# STM32F103CBT6.net
KiCad netlist of a schematic drawn in Altium Designer
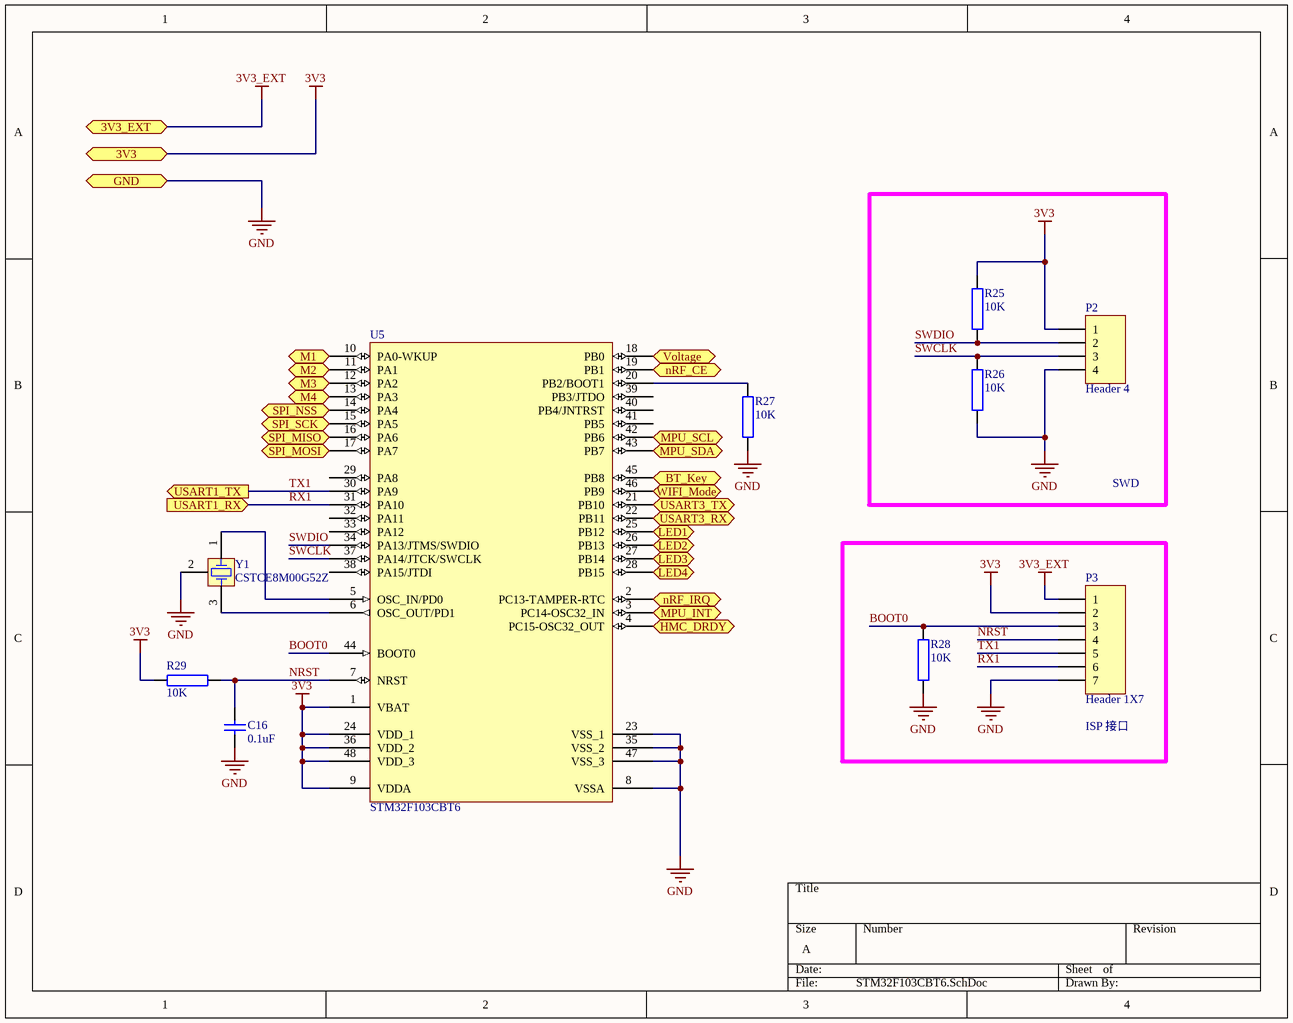
[diagram p0: STM32F103CBT6.SchDoc]

(export (version "E")
  (design (tool "Eeschema 10.0.6"))
  (components
    (comp (ref "C16")
      (value "0.1uF")
      (footprint "C0603")
      (description "Capacitor (Semiconductor SIM Model)")
      (fields (field (name "PUBLISHER") "Altium Limited"))
      (libsource (lib "Quadcopter") (part "Cap"))
    )
    (comp (ref "P2")
      (value "Header 4")
      (footprint "HDR1X4")
      (description "Header, 4-Pin")
      (fields (field (name "PUBLISHER") "Altium Limited"))
      (libsource (lib "Miscellaneous Connectors") (part "Header 4"))
    )
    (comp (ref "P3")
      (value "Header 1X7")
      (footprint "HDR1X7")
      (description "Header, 7-Pin")
      (fields (field (name "PUBLISHER") "Altium Limited"))
      (libsource (lib "Quadcopter") (part "Header 1X7"))
    )
    (comp (ref "R25")
      (value "10K")
      (footprint "R0603")
      (description "Resistor")
      (fields (field (name "PUBLISHER") "Altium Limited"))
      (libsource (lib "Quadcopter") (part "Res3"))
    )
    (comp (ref "R26")
      (value "10K")
      (footprint "R0603")
      (description "Resistor")
      (fields (field (name "PUBLISHER") "Altium Limited"))
      (libsource (lib "Quadcopter") (part "Res3"))
    )
    (comp (ref "R27")
      (value "10K")
      (footprint "R0603")
      (description "Resistor")
      (fields (field (name "PUBLISHER") "Altium Limited"))
      (libsource (lib "Quadcopter") (part "Res3"))
    )
    (comp (ref "R28")
      (value "10K")
      (footprint "R0603")
      (description "Resistor")
      (fields (field (name "PUBLISHER") "Altium Limited"))
      (libsource (lib "Quadcopter") (part "Res3"))
    )
    (comp (ref "R29")
      (value "10K")
      (footprint "R0603")
      (description "Resistor")
      (fields (field (name "PUBLISHER") "Altium Limited"))
      (libsource (lib "Quadcopter") (part "Res3"))
    )
    (comp (ref "U5")
      (value "STM32F103CBT6")
      (footprint "LQFP48_N")
      (description "STM32 ARM-based 32-bit MCU with 128 Kbytes Flash, 48-pin LQFP, Industrial Temperature")
      (fields (field (name "PUBLISHER") "Altium Limited"))
      (libsource (lib "ST Microcontroller 32-Bit STM32") (part "STM32F103CBT6"))
    )
    (comp (ref "Y1")
      (value "CSTCE8M00G52Z")
      (footprint "X8MCSTCR")
      (description "Crystal Oscillator, 3rd In-Line Lead Version")
      (libsource (lib "Quadcopter") (part "CSTCE8M00G52Z"))
    )
  )
  (nets
    (net (code "1") (name "/BOOT0") (class "Default")
      (node (ref "P3") (pin "3") (pinfunction "3_3") (pintype "passive"))
      (node (ref "R28") (pin "1") (pinfunction "1_1") (pintype "passive"))
      (node (ref "U5") (pin "44") (pinfunction "BOOT0_44") (pintype "input"))
    )
    (net (code "2") (name "/BT_Key") (class "Default")
      (node (ref "U5") (pin "45") (pinfunction "PB8_45") (pintype "bidirectional"))
    )
    (net (code "3") (name "/HMC_DRDY") (class "Default")
      (node (ref "U5") (pin "4") (pinfunction "PC15-OSC32_OUT_4") (pintype "bidirectional"))
    )
    (net (code "4") (name "/LED1") (class "Default")
      (node (ref "U5") (pin "25") (pinfunction "PB12_25") (pintype "bidirectional"))
    )
    (net (code "5") (name "/LED2") (class "Default")
      (node (ref "U5") (pin "26") (pinfunction "PB13_26") (pintype "bidirectional"))
    )
    (net (code "6") (name "/LED3") (class "Default")
      (node (ref "U5") (pin "27") (pinfunction "PB14_27") (pintype "bidirectional"))
    )
    (net (code "7") (name "/LED4") (class "Default")
      (node (ref "U5") (pin "28") (pinfunction "PB15_28") (pintype "bidirectional"))
    )
    (net (code "8") (name "/M1") (class "Default")
      (node (ref "U5") (pin "10") (pinfunction "PA0-WKUP_10") (pintype "bidirectional"))
    )
    (net (code "9") (name "/M2") (class "Default")
      (node (ref "U5") (pin "11") (pinfunction "PA1_11") (pintype "bidirectional"))
    )
    (net (code "10") (name "/M3") (class "Default")
      (node (ref "U5") (pin "12") (pinfunction "PA2_12") (pintype "bidirectional"))
    )
    (net (code "11") (name "/M4") (class "Default")
      (node (ref "U5") (pin "13") (pinfunction "PA3_13") (pintype "bidirectional"))
    )
    (net (code "12") (name "/MPU_INT") (class "Default")
      (node (ref "U5") (pin "3") (pinfunction "PC14-OSC32_IN_3") (pintype "bidirectional"))
    )
    (net (code "13") (name "/MPU_SCL") (class "Default")
      (node (ref "U5") (pin "42") (pinfunction "PB6_42") (pintype "bidirectional"))
    )
    (net (code "14") (name "/MPU_SDA") (class "Default")
      (node (ref "U5") (pin "43") (pinfunction "PB7_43") (pintype "bidirectional"))
    )
    (net (code "15") (name "/NRST") (class "Default")
      (node (ref "C16") (pin "2") (pinfunction "2_2") (pintype "passive"))
      (node (ref "P3") (pin "4") (pinfunction "4_4") (pintype "passive"))
      (node (ref "R29") (pin "2") (pinfunction "2_2") (pintype "passive"))
      (node (ref "U5") (pin "7") (pinfunction "NRST_7") (pintype "bidirectional"))
    )
    (net (code "16") (name "/RX1") (class "Default")
      (node (ref "P3") (pin "6") (pinfunction "6_6") (pintype "passive"))
      (node (ref "U5") (pin "31") (pinfunction "PA10_31") (pintype "bidirectional"))
    )
    (net (code "17") (name "/SPI_MISO") (class "Default")
      (node (ref "U5") (pin "16") (pinfunction "PA6_16") (pintype "bidirectional"))
    )
    (net (code "18") (name "/SPI_MOSI") (class "Default")
      (node (ref "U5") (pin "17") (pinfunction "PA7_17") (pintype "bidirectional"))
    )
    (net (code "19") (name "/SPI_NSS") (class "Default")
      (node (ref "U5") (pin "14") (pinfunction "PA4_14") (pintype "bidirectional"))
    )
    (net (code "20") (name "/SPI_SCK") (class "Default")
      (node (ref "U5") (pin "15") (pinfunction "PA5_15") (pintype "bidirectional"))
    )
    (net (code "21") (name "/SWCLK") (class "Default")
      (node (ref "P2") (pin "3") (pinfunction "3_3") (pintype "passive"))
      (node (ref "R26") (pin "2") (pinfunction "2_2") (pintype "passive"))
      (node (ref "U5") (pin "37") (pinfunction "PA14/JTCK/SWCLK_37") (pintype "bidirectional"))
    )
    (net (code "22") (name "/SWDIO") (class "Default")
      (node (ref "P2") (pin "2") (pinfunction "2_2") (pintype "passive"))
      (node (ref "R25") (pin "1") (pinfunction "1_1") (pintype "passive"))
      (node (ref "U5") (pin "34") (pinfunction "PA13/JTMS/SWDIO_34") (pintype "bidirectional"))
    )
    (net (code "23") (name "/TX1") (class "Default")
      (node (ref "P3") (pin "5") (pinfunction "5_5") (pintype "passive"))
      (node (ref "U5") (pin "30") (pinfunction "PA9_30") (pintype "bidirectional"))
    )
    (net (code "24") (name "/USART3_RX") (class "Default")
      (node (ref "U5") (pin "22") (pinfunction "PB11_22") (pintype "bidirectional"))
    )
    (net (code "25") (name "/USART3_TX") (class "Default")
      (node (ref "U5") (pin "21") (pinfunction "PB10_21") (pintype "bidirectional"))
    )
    (net (code "26") (name "/Voltage") (class "Default")
      (node (ref "U5") (pin "18") (pinfunction "PB0_18") (pintype "bidirectional"))
    )
    (net (code "27") (name "/WIFI_Mode") (class "Default")
      (node (ref "U5") (pin "46") (pinfunction "PB9_46") (pintype "bidirectional"))
    )
    (net (code "28") (name "/nRF_CE") (class "Default")
      (node (ref "U5") (pin "19") (pinfunction "PB1_19") (pintype "bidirectional"))
    )
    (net (code "29") (name "/nRF_IRQ") (class "Default")
      (node (ref "U5") (pin "2") (pinfunction "PC13-TAMPER-RTC_2") (pintype "bidirectional"))
    )
    (net (code "30") (name "3V3") (class "Default")
      (node (ref "P2") (pin "1") (pinfunction "1_1") (pintype "passive"))
      (node (ref "P3") (pin "2") (pinfunction "2_2") (pintype "passive"))
      (node (ref "R25") (pin "2") (pinfunction "2_2") (pintype "passive"))
      (node (ref "R29") (pin "1") (pinfunction "1_1") (pintype "passive"))
      (node (ref "U5") (pin "1") (pinfunction "VBAT_1") (pintype "power_in"))
      (node (ref "U5") (pin "24") (pinfunction "VDD_1_24") (pintype "power_in"))
      (node (ref "U5") (pin "36") (pinfunction "VDD_2_36") (pintype "power_in"))
      (node (ref "U5") (pin "48") (pinfunction "VDD_3_48") (pintype "power_in"))
      (node (ref "U5") (pin "9") (pinfunction "VDDA_9") (pintype "power_in"))
    )
    (net (code "31") (name "3V3_EXT") (class "Default")
      (node (ref "P3") (pin "1") (pinfunction "1_1") (pintype "passive"))
    )
    (net (code "32") (name "GND") (class "Default")
      (node (ref "C16") (pin "1") (pinfunction "1_1") (pintype "passive"))
      (node (ref "P2") (pin "4") (pinfunction "4_4") (pintype "passive"))
      (node (ref "P3") (pin "7") (pinfunction "7_7") (pintype "passive"))
      (node (ref "R26") (pin "1") (pinfunction "1_1") (pintype "passive"))
      (node (ref "R27") (pin "1") (pinfunction "1_1") (pintype "passive"))
      (node (ref "R28") (pin "2") (pinfunction "2_2") (pintype "passive"))
      (node (ref "U5") (pin "23") (pinfunction "VSS_1_23") (pintype "power_in"))
      (node (ref "U5") (pin "35") (pinfunction "VSS_2_35") (pintype "power_in"))
      (node (ref "U5") (pin "47") (pinfunction "VSS_3_47") (pintype "power_in"))
      (node (ref "U5") (pin "8") (pinfunction "VSSA_8") (pintype "power_in"))
      (node (ref "Y1") (pin "2") (pinfunction "COM_2") (pintype "passive"))
    )
    (net (code "33") (name "Net-(U5-OSC_IN{slash}PD0)") (class "Default")
      (node (ref "U5") (pin "5") (pinfunction "OSC_IN/PD0_5") (pintype "input"))
      (node (ref "Y1") (pin "1") (pinfunction "OSC1_1") (pintype "passive"))
    )
    (net (code "34") (name "Net-(U5-OSC_OUT{slash}PD1)") (class "Default")
      (node (ref "U5") (pin "6") (pinfunction "OSC_OUT/PD1_6") (pintype "output"))
      (node (ref "Y1") (pin "3") (pinfunction "OSC2_3") (pintype "passive"))
    )
    (net (code "35") (name "Net-(U5-PB2{slash}BOOT1)") (class "Default")
      (node (ref "R27") (pin "2") (pinfunction "2_2") (pintype "passive"))
      (node (ref "U5") (pin "20") (pinfunction "PB2/BOOT1_20") (pintype "bidirectional"))
    )
    (net (code "36") (name "unconnected-(U5-PA8-Pad29)") (class "Default")
      (node (ref "U5") (pin "29") (pinfunction "PA8_29") (pintype "bidirectional"))
    )
    (net (code "37") (name "unconnected-(U5-PA11-Pad32)") (class "Default")
      (node (ref "U5") (pin "32") (pinfunction "PA11_32") (pintype "bidirectional"))
    )
    (net (code "38") (name "unconnected-(U5-PA12-Pad33)") (class "Default")
      (node (ref "U5") (pin "33") (pinfunction "PA12_33") (pintype "bidirectional"))
    )
    (net (code "39") (name "unconnected-(U5-PA15{slash}JTDI-Pad38)") (class "Default")
      (node (ref "U5") (pin "38") (pinfunction "PA15/JTDI_38") (pintype "bidirectional"))
    )
    (net (code "40") (name "unconnected-(U5-PB3{slash}JTDO-Pad39)") (class "Default")
      (node (ref "U5") (pin "39") (pinfunction "PB3/JTDO_39") (pintype "bidirectional"))
    )
    (net (code "41") (name "unconnected-(U5-PB4{slash}JNTRST-Pad40)") (class "Default")
      (node (ref "U5") (pin "40") (pinfunction "PB4/JNTRST_40") (pintype "bidirectional"))
    )
    (net (code "42") (name "unconnected-(U5-PB5-Pad41)") (class "Default")
      (node (ref "U5") (pin "41") (pinfunction "PB5_41") (pintype "bidirectional"))
    )
  )
)
